# Lid_Simulator.net
KiCad netlist of a schematic drawn in EAGLE
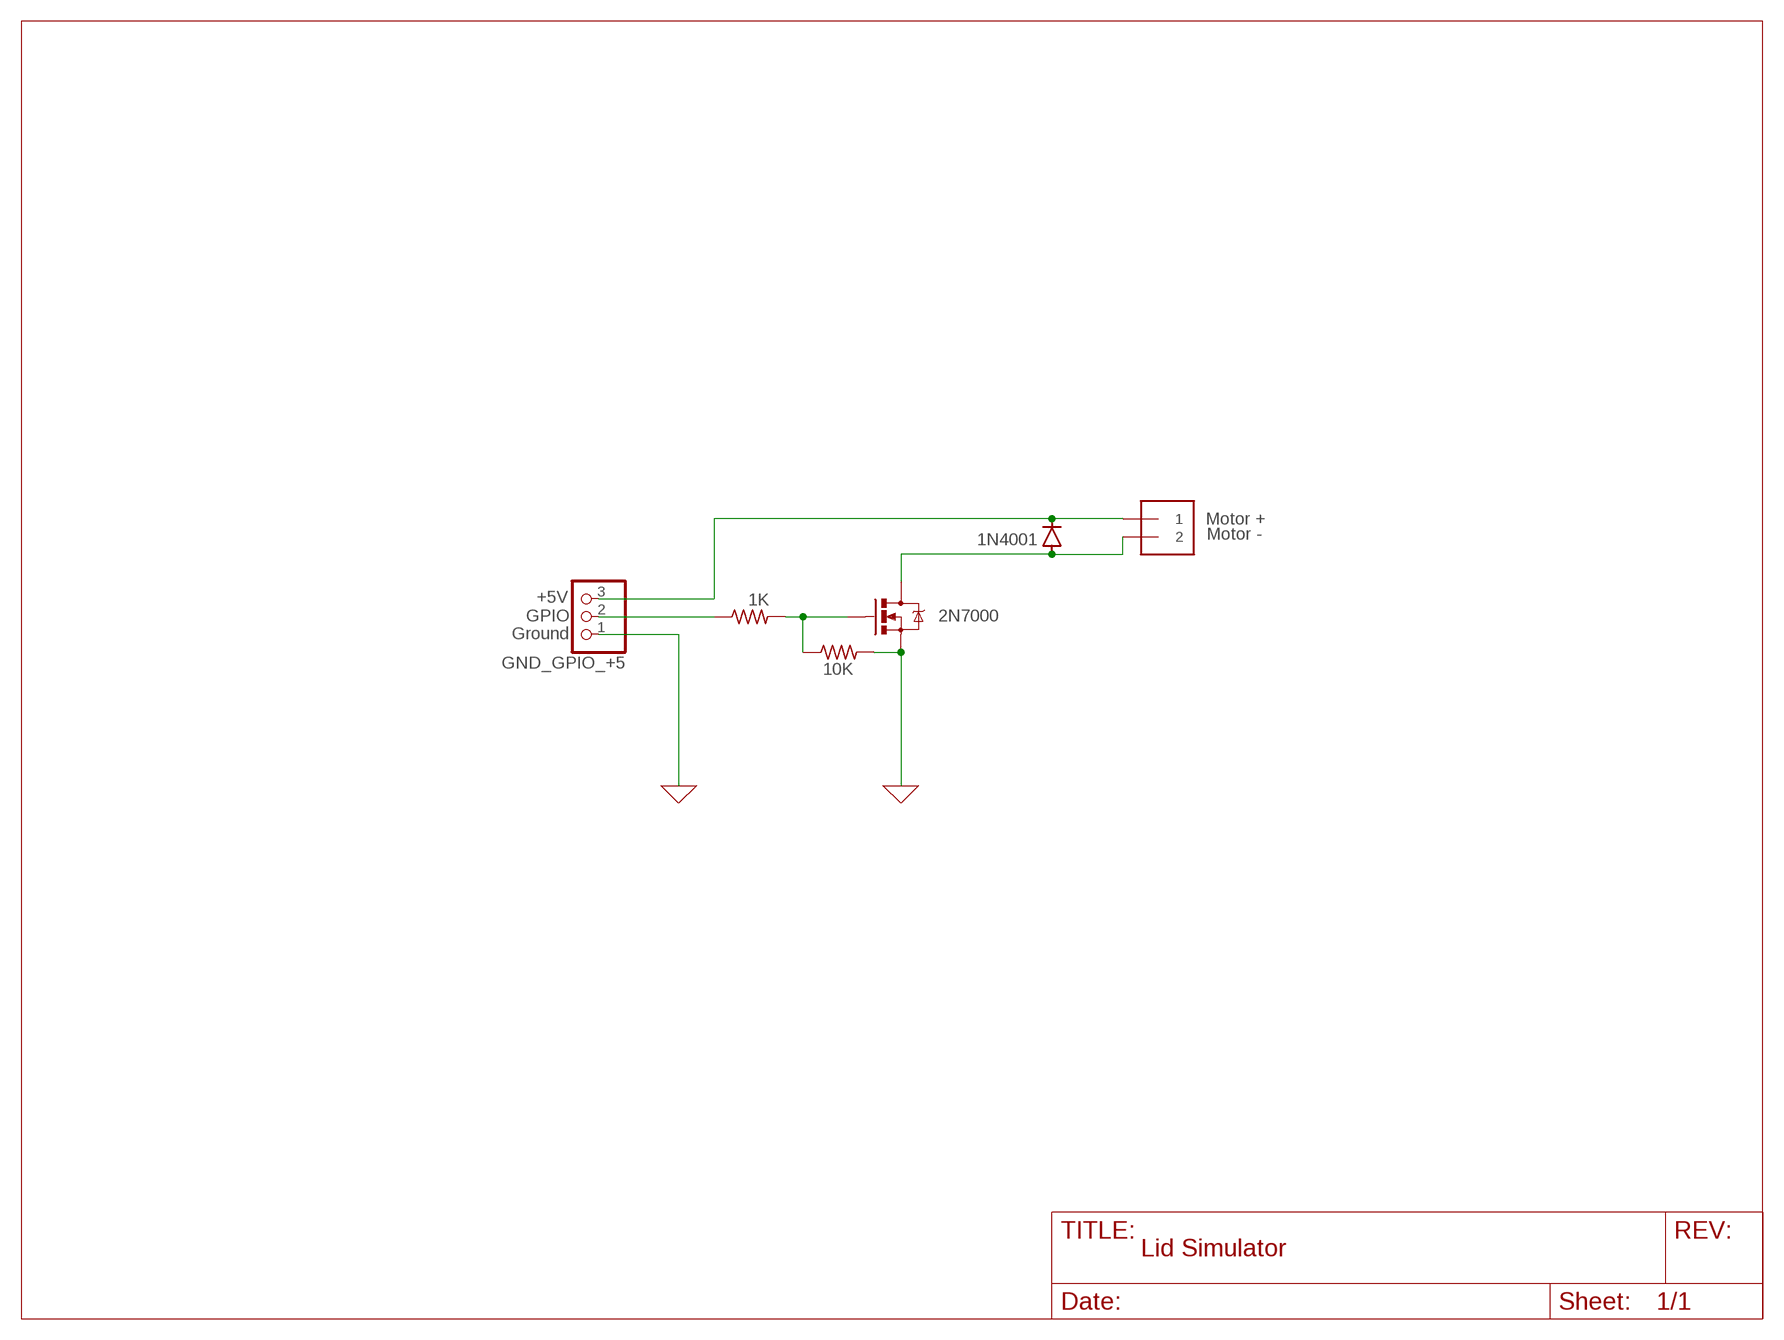
[diagram p0: schematic, sheet 1]

(export (version "E")
  (design (tool "Eeschema 10.0.6"))
  (components
    (comp (ref "D1")
      (value "1N4001")
      (footprint "eagle-import:DO-41")
      (fields
        (field (name "DIGIKEY_PART_NUMBER") "1N4004MSCT-ND")
        (field (name "MANUFACTURER") "Micro Commercial Co")
        (field (name "MPN") "1N4004")
        (field (name "CREATED_BY") "PCBLayout.com")
      )
      (libsource (lib "eagle-import") (part "1N4004"))
    )
    (comp (ref "GND_GPIO_+5")
      (value "PINHD-1X3CB")
      (footprint "eagle-import:1X03-CLEANBIG")
      (libsource (lib "eagle-import") (part "PINHD-1X3CB"))
    )
    (comp (ref "MOTOR_-__+")
      (value "1X2-3.5MM")
      (footprint "eagle-import:1X2-3.5MM")
      (libsource (lib "eagle-import") (part "1X2-3.5MM"))
    )
    (comp (ref "Q1")
      (value "MOSFET-NCHANNEL2N7000")
      (footprint "eagle-import:TO-92")
      (libsource (lib "eagle-import") (part "MOSFET-NCHANNEL2N7000"))
    )
    (comp (ref "R1")
      (value "1K")
      (footprint "eagle-import:0207_10")
      (libsource (lib "eagle-import") (part "R-US_0207/10"))
    )
    (comp (ref "R2")
      (value "10K")
      (footprint "eagle-import:0207_10")
      (libsource (lib "eagle-import") (part "R-US_0207/10"))
    )
  )
  (nets
    (net (code "1") (name "GND") (class "Default")
      (node (ref "GND_GPIO_+5") (pin "1") (pinfunction "1_1") (pintype "passive"))
      (node (ref "Q1") (pin "1") (pinfunction "S_1") (pintype "passive"))
      (node (ref "R2") (pin "2") (pinfunction "2_2") (pintype "passive"))
    )
    (net (code "2") (name "Net-(D1-PadC)") (class "Default")
      (node (ref "D1") (pin "C") (pinfunction "C_C") (pintype "passive"))
      (node (ref "GND_GPIO_+5") (pin "3") (pinfunction "3_3") (pintype "passive"))
      (node (ref "MOTOR_-__+") (pin "1") (pinfunction "1_1") (pintype "passive"))
    )
    (net (code "3") (name "Net-(GND_GPIO_+5-Pad2)") (class "Default")
      (node (ref "GND_GPIO_+5") (pin "2") (pinfunction "2_2") (pintype "passive"))
      (node (ref "R1") (pin "1") (pinfunction "1_1") (pintype "passive"))
    )
    (net (code "4") (name "Net-(Q1-D)") (class "Default")
      (node (ref "D1") (pin "A") (pinfunction "A_A") (pintype "passive"))
      (node (ref "MOTOR_-__+") (pin "2") (pinfunction "2_2") (pintype "passive"))
      (node (ref "Q1") (pin "3") (pinfunction "D_3") (pintype "passive"))
    )
    (net (code "5") (name "Net-(Q1-G)") (class "Default")
      (node (ref "Q1") (pin "2") (pinfunction "G_2") (pintype "passive"))
      (node (ref "R1") (pin "2") (pinfunction "2_2") (pintype "passive"))
      (node (ref "R2") (pin "1") (pinfunction "1_1") (pintype "passive"))
    )
  )
)
